# hdmi.net
KiCad netlist of a schematic drawn in Altium Designer
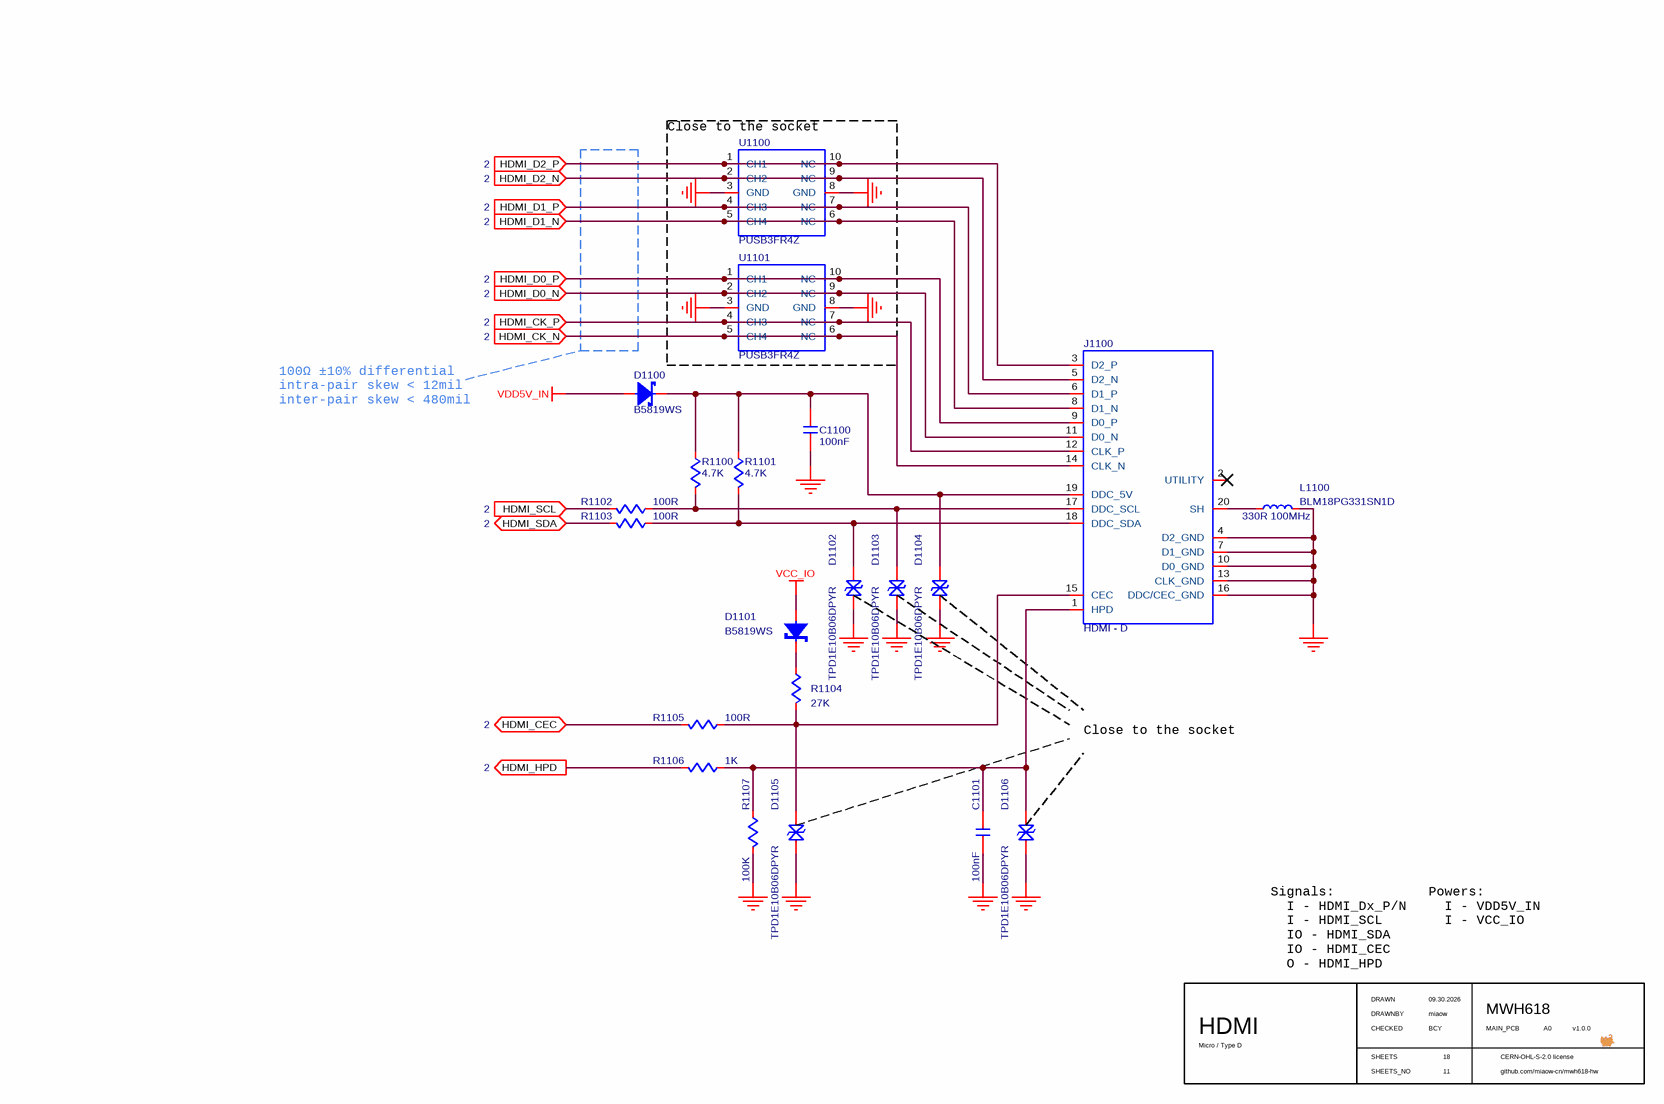
[diagram p0: hdmi.schdoc]

(export (version "E")
  (design (tool "Eeschema 10.0.6"))
  (components
    (comp (ref "C1100")
      (value "100nF")
      (footprint "mw:C0402")
      (fields (field (name "VOLTAGE") "50V") (field (name "Comment") "C-NOMO"))
      (libsource (lib "mw") (part "C-NOMO"))
    )
    (comp (ref "C1101")
      (value "100nF")
      (footprint "mw:C0402")
      (fields (field (name "VOLTAGE") "50V") (field (name "Comment") "C-NOMO"))
      (libsource (lib "mw") (part "C-NOMO"))
    )
    (comp (ref "D1100")
      (value "B5819WS")
      (footprint "mw:B5819WS")
      (description "SCHOTTKY")
      (libsource (lib "mw") (part "B5819WS"))
    )
    (comp (ref "D1101")
      (value "B5819WS")
      (footprint "mw:B5819WS")
      (description "SCHOTTKY")
      (libsource (lib "mw") (part "B5819WS"))
    )
    (comp (ref "D1102")
      (value "TPD1E10B06DPYR")
      (footprint "mw:TPD1E10B06DPYR")
      (description "TVS/ESD - 1 ch, 5.5V, 6V, 12pF@1MHz, 30KV")
      (libsource (lib "mw") (part "TPD1E10B06DPYR"))
    )
    (comp (ref "D1103")
      (value "TPD1E10B06DPYR")
      (footprint "mw:TPD1E10B06DPYR")
      (description "TVS/ESD - 1 ch, 5.5V, 6V, 12pF@1MHz, 30KV")
      (libsource (lib "mw") (part "TPD1E10B06DPYR"))
    )
    (comp (ref "D1104")
      (value "TPD1E10B06DPYR")
      (footprint "mw:TPD1E10B06DPYR")
      (description "TVS/ESD - 1 ch, 5.5V, 6V, 12pF@1MHz, 30KV")
      (libsource (lib "mw") (part "TPD1E10B06DPYR"))
    )
    (comp (ref "D1105")
      (value "TPD1E10B06DPYR")
      (footprint "mw:TPD1E10B06DPYR")
      (description "TVS/ESD - 1 ch, 5.5V, 6V, 12pF@1MHz, 30KV")
      (libsource (lib "mw") (part "TPD1E10B06DPYR"))
    )
    (comp (ref "D1106")
      (value "TPD1E10B06DPYR")
      (footprint "mw:TPD1E10B06DPYR")
      (description "TVS/ESD - 1 ch, 5.5V, 6V, 12pF@1MHz, 30KV")
      (libsource (lib "mw") (part "TPD1E10B06DPYR"))
    )
    (comp (ref "J1100") (value "HDMI - D") (footprint "mw:HDMI-D") (libsource (lib "mw") (part "HDMI")))
    (comp (ref "L1100")
      (value "BLM18PG331SN1D")
      (footprint "mw:L0603")
      (fields (field (name "ALTIUM_VALUE") "330R 100MHz") (field (name "PUBLISHER") "Altium Limited"))
      (libsource (lib "mw") (part "L"))
    )
    (comp (ref "R1100")
      (value "4.7K")
      (footprint "mw:R0402")
      (fields (field (name "Comment") "R"))
      (libsource (lib "mw") (part "R"))
    )
    (comp (ref "R1101")
      (value "4.7K")
      (footprint "mw:R0402")
      (fields (field (name "Comment") "R"))
      (libsource (lib "mw") (part "R"))
    )
    (comp (ref "R1102")
      (value "100R")
      (footprint "mw:R0402")
      (fields (field (name "Comment") "R"))
      (libsource (lib "mw") (part "R"))
    )
    (comp (ref "R1103")
      (value "100R")
      (footprint "mw:R0402")
      (fields (field (name "Comment") "R"))
      (libsource (lib "mw") (part "R"))
    )
    (comp (ref "R1104")
      (value "27K")
      (footprint "mw:R0402")
      (fields (field (name "Comment") "R"))
      (libsource (lib "mw") (part "R"))
    )
    (comp (ref "R1105")
      (value "100R")
      (footprint "mw:R0402")
      (fields (field (name "Comment") "R"))
      (libsource (lib "mw") (part "R"))
    )
    (comp (ref "R1106")
      (value "1K")
      (footprint "mw:R0402")
      (fields (field (name "Comment") "R"))
      (libsource (lib "mw") (part "R"))
    )
    (comp (ref "R1107")
      (value "100K")
      (footprint "mw:R0402")
      (fields (field (name "Comment") "R"))
      (libsource (lib "mw") (part "R"))
    )
    (comp (ref "U1100")
      (value "PUSB3FR4Z")
      (footprint "mw:PUSB3FR4Z")
      (description "TVS/ESD - 4 ch, 3.3V, 5.5V, 0.29pF@1MHz, 15KV")
      (libsource (lib "mw") (part "PUSB3FR4Z"))
    )
    (comp (ref "U1101")
      (value "PUSB3FR4Z")
      (footprint "mw:PUSB3FR4Z")
      (description "TVS/ESD - 4 ch, 3.3V, 5.5V, 0.29pF@1MHz, 15KV")
      (libsource (lib "mw") (part "PUSB3FR4Z"))
    )
  )
  (nets
    (net (code "1") (name "/HDMI_CEC") (class "Default")
      (node (ref "R1105") (pin "1") (pinfunction "1_1") (pintype "passive"))
    )
    (net (code "2") (name "/HDMI_CK_N") (class "Default")
      (node (ref "J1100") (pin "14") (pinfunction "CLK_N_14") (pintype "passive"))
      (node (ref "U1101") (pin "5") (pinfunction "CH4_5") (pintype "passive"))
      (node (ref "U1101") (pin "6") (pinfunction "NC_6") (pintype "passive"))
    )
    (net (code "3") (name "/HDMI_CK_P") (class "Default")
      (node (ref "J1100") (pin "12") (pinfunction "CLK_P_12") (pintype "passive"))
      (node (ref "U1101") (pin "4") (pinfunction "CH3_4") (pintype "passive"))
      (node (ref "U1101") (pin "7") (pinfunction "NC_7") (pintype "passive"))
    )
    (net (code "4") (name "/HDMI_D0_N") (class "Default")
      (node (ref "J1100") (pin "11") (pinfunction "D0_N_11") (pintype "passive"))
      (node (ref "U1101") (pin "2") (pinfunction "CH2_2") (pintype "passive"))
      (node (ref "U1101") (pin "9") (pinfunction "NC_9") (pintype "passive"))
    )
    (net (code "5") (name "/HDMI_D0_P") (class "Default")
      (node (ref "J1100") (pin "9") (pinfunction "D0_P_9") (pintype "passive"))
      (node (ref "U1101") (pin "1") (pinfunction "CH1_1") (pintype "passive"))
      (node (ref "U1101") (pin "10") (pinfunction "NC_10") (pintype "passive"))
    )
    (net (code "6") (name "/HDMI_D1_N") (class "Default")
      (node (ref "J1100") (pin "8") (pinfunction "D1_N_8") (pintype "passive"))
      (node (ref "U1100") (pin "5") (pinfunction "CH4_5") (pintype "passive"))
      (node (ref "U1100") (pin "6") (pinfunction "NC_6") (pintype "passive"))
    )
    (net (code "7") (name "/HDMI_D1_P") (class "Default")
      (node (ref "J1100") (pin "6") (pinfunction "D1_P_6") (pintype "passive"))
      (node (ref "U1100") (pin "4") (pinfunction "CH3_4") (pintype "passive"))
      (node (ref "U1100") (pin "7") (pinfunction "NC_7") (pintype "passive"))
    )
    (net (code "8") (name "/HDMI_D2_N") (class "Default")
      (node (ref "J1100") (pin "5") (pinfunction "D2_N_5") (pintype "passive"))
      (node (ref "U1100") (pin "2") (pinfunction "CH2_2") (pintype "passive"))
      (node (ref "U1100") (pin "9") (pinfunction "NC_9") (pintype "passive"))
    )
    (net (code "9") (name "/HDMI_D2_P") (class "Default")
      (node (ref "J1100") (pin "3") (pinfunction "D2_P_3") (pintype "passive"))
      (node (ref "U1100") (pin "1") (pinfunction "CH1_1") (pintype "passive"))
      (node (ref "U1100") (pin "10") (pinfunction "NC_10") (pintype "passive"))
    )
    (net (code "10") (name "/HDMI_HPD") (class "Default")
      (node (ref "R1106") (pin "1") (pinfunction "1_1") (pintype "passive"))
    )
    (net (code "11") (name "/HDMI_SCL") (class "Default")
      (node (ref "R1102") (pin "1") (pinfunction "1_1") (pintype "passive"))
    )
    (net (code "12") (name "/HDMI_SDA") (class "Default")
      (node (ref "R1103") (pin "1") (pinfunction "1_1") (pintype "passive"))
    )
    (net (code "13") (name "GND") (class "Default")
      (node (ref "C1100") (pin "1") (pinfunction "1_1") (pintype "passive"))
      (node (ref "C1101") (pin "1") (pinfunction "1_1") (pintype "passive"))
      (node (ref "D1102") (pin "1") (pinfunction "1_1") (pintype "passive"))
      (node (ref "D1103") (pin "1") (pinfunction "1_1") (pintype "passive"))
      (node (ref "D1104") (pin "1") (pinfunction "1_1") (pintype "passive"))
      (node (ref "D1105") (pin "1") (pinfunction "1_1") (pintype "passive"))
      (node (ref "D1106") (pin "1") (pinfunction "1_1") (pintype "passive"))
      (node (ref "J1100") (pin "10") (pinfunction "D0_GND_10") (pintype "passive"))
      (node (ref "J1100") (pin "13") (pinfunction "CLK_GND_13") (pintype "passive"))
      (node (ref "J1100") (pin "16") (pinfunction "DDC/CEC_GND_16") (pintype "passive"))
      (node (ref "J1100") (pin "4") (pinfunction "D2_GND_4") (pintype "passive"))
      (node (ref "J1100") (pin "7") (pinfunction "D1_GND_7") (pintype "passive"))
      (node (ref "L1100") (pin "2") (pinfunction "2_2") (pintype "passive"))
      (node (ref "R1107") (pin "1") (pinfunction "1_1") (pintype "passive"))
      (node (ref "U1100") (pin "3") (pinfunction "GND_3") (pintype "passive"))
      (node (ref "U1100") (pin "8") (pinfunction "GND_8") (pintype "passive"))
      (node (ref "U1101") (pin "3") (pinfunction "GND_3") (pintype "passive"))
      (node (ref "U1101") (pin "8") (pinfunction "GND_8") (pintype "passive"))
    )
    (net (code "14") (name "Net-(D1101-Pad1)") (class "Default")
      (node (ref "D1101") (pin "1") (pinfunction "1_1") (pintype "passive"))
      (node (ref "R1104") (pin "2") (pinfunction "2_2") (pintype "passive"))
    )
    (net (code "15") (name "Net-(J1100-CEC)") (class "Default")
      (node (ref "D1105") (pin "2") (pinfunction "2_2") (pintype "passive"))
      (node (ref "J1100") (pin "15") (pinfunction "CEC_15") (pintype "passive"))
      (node (ref "R1104") (pin "1") (pinfunction "1_1") (pintype "passive"))
      (node (ref "R1105") (pin "2") (pinfunction "2_2") (pintype "passive"))
    )
    (net (code "16") (name "Net-(J1100-DDC_5V)") (class "Default")
      (node (ref "C1100") (pin "2") (pinfunction "2_2") (pintype "passive"))
      (node (ref "D1100") (pin "1") (pinfunction "1_1") (pintype "passive"))
      (node (ref "D1104") (pin "2") (pinfunction "2_2") (pintype "passive"))
      (node (ref "J1100") (pin "19") (pinfunction "DDC_5V_19") (pintype "passive"))
      (node (ref "R1100") (pin "2") (pinfunction "2_2") (pintype "passive"))
      (node (ref "R1101") (pin "2") (pinfunction "2_2") (pintype "passive"))
    )
    (net (code "17") (name "Net-(J1100-DDC_SCL)") (class "Default")
      (node (ref "D1103") (pin "2") (pinfunction "2_2") (pintype "passive"))
      (node (ref "J1100") (pin "17") (pinfunction "DDC_SCL_17") (pintype "passive"))
      (node (ref "R1100") (pin "1") (pinfunction "1_1") (pintype "passive"))
      (node (ref "R1102") (pin "2") (pinfunction "2_2") (pintype "passive"))
    )
    (net (code "18") (name "Net-(J1100-DDC_SDA)") (class "Default")
      (node (ref "D1102") (pin "2") (pinfunction "2_2") (pintype "passive"))
      (node (ref "J1100") (pin "18") (pinfunction "DDC_SDA_18") (pintype "passive"))
      (node (ref "R1101") (pin "1") (pinfunction "1_1") (pintype "passive"))
      (node (ref "R1103") (pin "2") (pinfunction "2_2") (pintype "passive"))
    )
    (net (code "19") (name "Net-(J1100-HPD)") (class "Default")
      (node (ref "C1101") (pin "2") (pinfunction "2_2") (pintype "passive"))
      (node (ref "D1106") (pin "2") (pinfunction "2_2") (pintype "passive"))
      (node (ref "J1100") (pin "1") (pinfunction "HPD_1") (pintype "passive"))
      (node (ref "R1106") (pin "2") (pinfunction "2_2") (pintype "passive"))
      (node (ref "R1107") (pin "2") (pinfunction "2_2") (pintype "passive"))
    )
    (net (code "20") (name "Net-(J1100-SH)") (class "Default")
      (node (ref "J1100") (pin "20") (pinfunction "SH_20") (pintype "passive"))
      (node (ref "L1100") (pin "1") (pinfunction "1_1") (pintype "passive"))
    )
    (net (code "21") (name "VCC_IO") (class "Default")
      (node (ref "D1101") (pin "2") (pinfunction "2_2") (pintype "passive"))
    )
    (net (code "22") (name "VDD5V_IN") (class "Default")
      (node (ref "D1100") (pin "2") (pinfunction "2_2") (pintype "passive"))
    )
    (net (code "23") (name "unconnected-(J1100-UTILITY-Pad2)") (class "Default")
      (node (ref "J1100") (pin "2") (pinfunction "UTILITY_2") (pintype "passive+no_connect"))
    )
  )
)
